# Controller.net
KiCad netlist of a schematic drawn in EAGLE
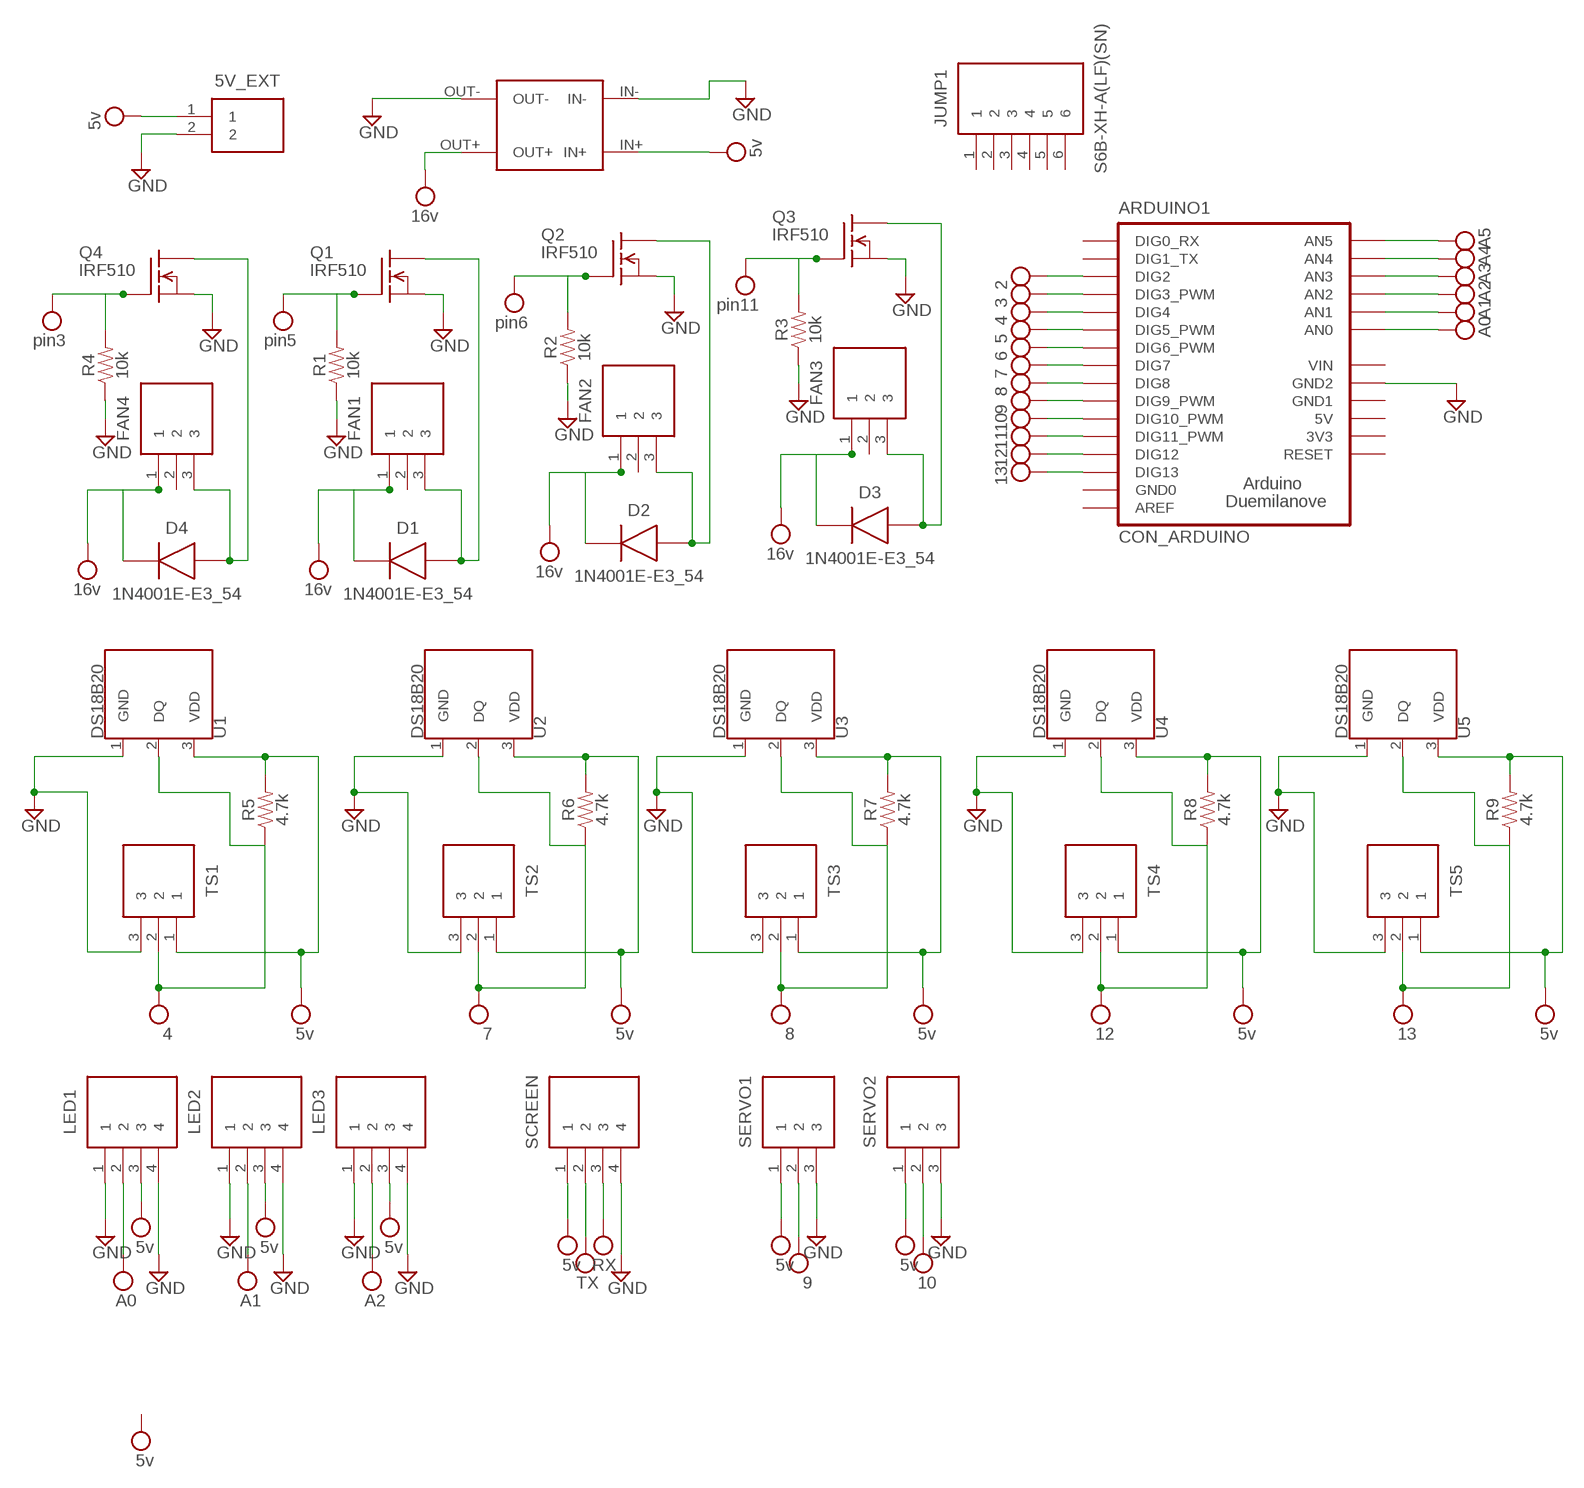
[diagram p0: schematic, sheet 1]
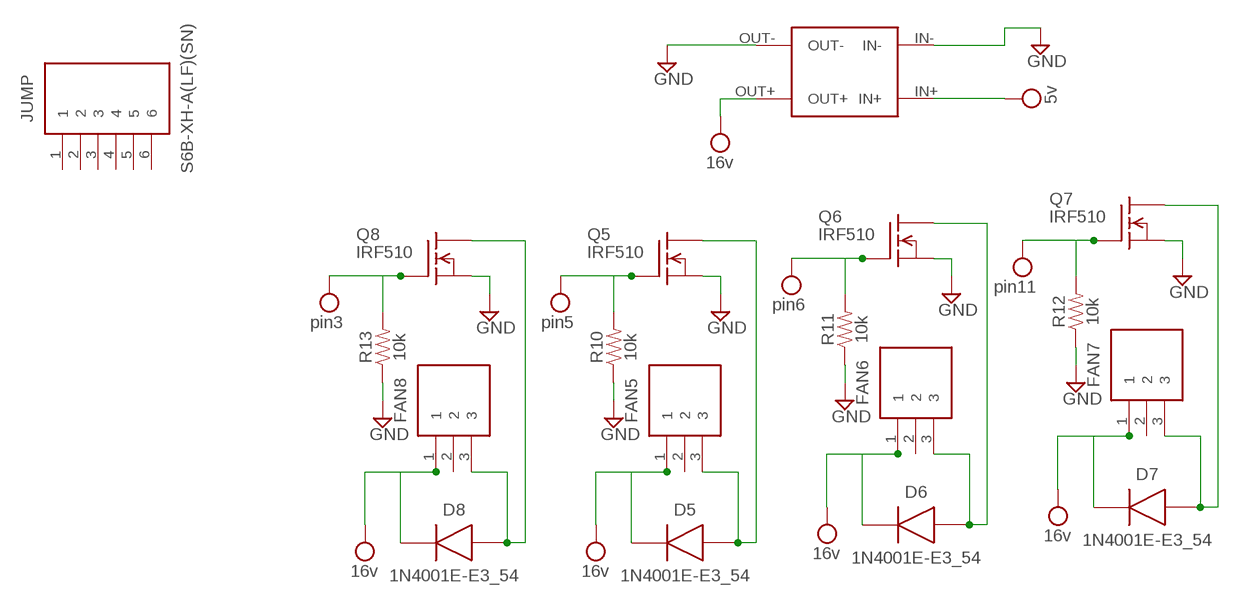
[diagram p1: schematic, sheet 2]

(export (version "E")
  (design (tool "Eeschema 10.0.6"))
  (components
    (comp (ref "5V_EXT")
      (value "S2B-XH-A(LF)(SN)")
      (footprint "eagle-import:SHDR2W80P0X250_1X2_740X575X700")
      (fields (field (name "RS_PART_NUMBER") "8201582"))
      (libsource (lib "eagle-import") (part "S2B-XH-A(LF)(SN)"))
    )
    (comp (ref "ARDUINO1")
      (value "CON_ARDUINO")
      (footprint "eagle-import:CON_ARDUINO")
      (libsource (lib "eagle-import") (part "CON_ARDUINO"))
    )
    (comp (ref "D1")
      (value "1N4001E-E3_54")
      (footprint "eagle-import:DIOAD1405W86L465D235")
      (fields (field (name "MANUFACTURER_PART_NUMBER") "1N4001E-E3/54"))
      (libsource (lib "eagle-import") (part "1N4001E-E3_54"))
    )
    (comp (ref "D2")
      (value "1N4001E-E3_54")
      (footprint "eagle-import:DIOAD1405W86L465D235")
      (fields (field (name "MANUFACTURER_PART_NUMBER") "1N4001E-E3/54"))
      (libsource (lib "eagle-import") (part "1N4001E-E3_54"))
    )
    (comp (ref "D3")
      (value "1N4001E-E3_54")
      (footprint "eagle-import:DIOAD1405W86L465D235")
      (fields (field (name "MANUFACTURER_PART_NUMBER") "1N4001E-E3/54"))
      (libsource (lib "eagle-import") (part "1N4001E-E3_54"))
    )
    (comp (ref "D4")
      (value "1N4001E-E3_54")
      (footprint "eagle-import:DIOAD1405W86L465D235")
      (fields (field (name "MANUFACTURER_PART_NUMBER") "1N4001E-E3/54"))
      (libsource (lib "eagle-import") (part "1N4001E-E3_54"))
    )
    (comp (ref "FAN1")
      (value "S3B-XH-A(LF)(SN)")
      (footprint "eagle-import:SHDR3W80P0X250_1X3_990X610X700")
      (fields (field (name "RS_PART_NUMBER") "8201585"))
      (libsource (lib "eagle-import") (part "S3B-XH-A(LF)(SN)"))
    )
    (comp (ref "FAN2")
      (value "S3B-XH-A(LF)(SN)")
      (footprint "eagle-import:SHDR3W80P0X250_1X3_990X610X700")
      (fields (field (name "RS_PART_NUMBER") "8201585"))
      (libsource (lib "eagle-import") (part "S3B-XH-A(LF)(SN)"))
    )
    (comp (ref "FAN3")
      (value "S3B-XH-A(LF)(SN)")
      (footprint "eagle-import:SHDR3W80P0X250_1X3_990X610X700")
      (fields (field (name "RS_PART_NUMBER") "8201585"))
      (libsource (lib "eagle-import") (part "S3B-XH-A(LF)(SN)"))
    )
    (comp (ref "FAN4")
      (value "S3B-XH-A(LF)(SN)")
      (footprint "eagle-import:SHDR3W80P0X250_1X3_990X610X700")
      (fields (field (name "RS_PART_NUMBER") "8201585"))
      (libsource (lib "eagle-import") (part "S3B-XH-A(LF)(SN)"))
    )
    (comp (ref "JUMP1")
      (value "S6B-XH-A(LF)(SN)")
      (footprint "eagle-import:SHDR6W64P0X250_1X6_1740X1155X7")
      (fields (field (name "RS_PART_NUMBER") "8201591"))
      (libsource (lib "eagle-import") (part "S6B-XH-A(LF)(SN)"))
    )
    (comp (ref "LED1")
      (value "S4B-XH-A(LF)(SN)")
      (footprint "eagle-import:SHDR4W64P0X250_1X4_1240X1155X7")
      (fields (field (name "RS_PART_NUMBER") "8201589"))
      (libsource (lib "eagle-import") (part "S4B-XH-A(LF)(SN)"))
    )
    (comp (ref "LED2")
      (value "S4B-XH-A(LF)(SN)")
      (footprint "eagle-import:SHDR4W64P0X250_1X4_1240X1155X7")
      (fields (field (name "RS_PART_NUMBER") "8201589"))
      (libsource (lib "eagle-import") (part "S4B-XH-A(LF)(SN)"))
    )
    (comp (ref "LED3")
      (value "S4B-XH-A(LF)(SN)")
      (footprint "eagle-import:SHDR4W64P0X250_1X4_1240X1155X7")
      (fields (field (name "RS_PART_NUMBER") "8201589"))
      (libsource (lib "eagle-import") (part "S4B-XH-A(LF)(SN)"))
    )
    (comp (ref "Q1")
      (value "IRF510")
      (footprint "eagle-import:TO220")
      (libsource (lib "eagle-import") (part "IRF510"))
    )
    (comp (ref "Q2")
      (value "IRF510")
      (footprint "eagle-import:TO220")
      (libsource (lib "eagle-import") (part "IRF510"))
    )
    (comp (ref "Q3")
      (value "IRF510")
      (footprint "eagle-import:TO220")
      (libsource (lib "eagle-import") (part "IRF510"))
    )
    (comp (ref "Q4")
      (value "IRF510")
      (footprint "eagle-import:TO220")
      (libsource (lib "eagle-import") (part "IRF510"))
    )
    (comp (ref "R1")
      (value "10k")
      (footprint "eagle-import:AXIAL-0.3")
      (libsource (lib "eagle-import") (part "10KOHM-HORIZ-1/4W-5%"))
    )
    (comp (ref "R2")
      (value "10k")
      (footprint "eagle-import:AXIAL-0.3")
      (libsource (lib "eagle-import") (part "10KOHM-HORIZ-1/4W-5%"))
    )
    (comp (ref "R3")
      (value "10k")
      (footprint "eagle-import:AXIAL-0.3")
      (libsource (lib "eagle-import") (part "10KOHM-HORIZ-1/4W-5%"))
    )
    (comp (ref "R4")
      (value "10k")
      (footprint "eagle-import:AXIAL-0.3")
      (libsource (lib "eagle-import") (part "10KOHM-HORIZ-1/4W-5%"))
    )
    (comp (ref "R5")
      (value "4.7k")
      (footprint "eagle-import:AXIAL-0.3")
      (libsource (lib "eagle-import") (part "10KOHM-HORIZ-1/4W-5%"))
    )
    (comp (ref "R6")
      (value "4.7k")
      (footprint "eagle-import:AXIAL-0.3")
      (libsource (lib "eagle-import") (part "10KOHM-HORIZ-1/4W-5%"))
    )
    (comp (ref "R7")
      (value "4.7k")
      (footprint "eagle-import:AXIAL-0.3")
      (libsource (lib "eagle-import") (part "10KOHM-HORIZ-1/4W-5%"))
    )
    (comp (ref "R8")
      (value "4.7k")
      (footprint "eagle-import:AXIAL-0.3")
      (libsource (lib "eagle-import") (part "10KOHM-HORIZ-1/4W-5%"))
    )
    (comp (ref "R9")
      (value "4.7k")
      (footprint "eagle-import:AXIAL-0.3")
      (libsource (lib "eagle-import") (part "10KOHM-HORIZ-1/4W-5%"))
    )
    (comp (ref "SCREEN")
      (value "S4B-XH-A(LF)(SN)")
      (footprint "eagle-import:SHDR4W64P0X250_1X4_1240X1155X7")
      (fields (field (name "RS_PART_NUMBER") "8201589"))
      (libsource (lib "eagle-import") (part "S4B-XH-A(LF)(SN)"))
    )
    (comp (ref "SERVO1")
      (value "S3B-XH-A(LF)(SN)")
      (footprint "eagle-import:SHDR3W80P0X250_1X3_990X610X700")
      (fields (field (name "RS_PART_NUMBER") "8201585"))
      (libsource (lib "eagle-import") (part "S3B-XH-A(LF)(SN)"))
    )
    (comp (ref "SERVO2")
      (value "S3B-XH-A(LF)(SN)")
      (footprint "eagle-import:SHDR3W80P0X250_1X3_990X610X700")
      (fields (field (name "RS_PART_NUMBER") "8201585"))
      (libsource (lib "eagle-import") (part "S3B-XH-A(LF)(SN)"))
    )
    (comp (ref "TS1")
      (value "S3B-XH-A(LF)(SN)")
      (footprint "eagle-import:SHDR3W80P0X250_1X3_990X610X700")
      (fields (field (name "RS_PART_NUMBER") "8201585"))
      (libsource (lib "eagle-import") (part "S3B-XH-A(LF)(SN)"))
    )
    (comp (ref "TS2")
      (value "S3B-XH-A(LF)(SN)")
      (footprint "eagle-import:SHDR3W80P0X250_1X3_990X610X700")
      (fields (field (name "RS_PART_NUMBER") "8201585"))
      (libsource (lib "eagle-import") (part "S3B-XH-A(LF)(SN)"))
    )
    (comp (ref "TS3")
      (value "S3B-XH-A(LF)(SN)")
      (footprint "eagle-import:SHDR3W80P0X250_1X3_990X610X700")
      (fields (field (name "RS_PART_NUMBER") "8201585"))
      (libsource (lib "eagle-import") (part "S3B-XH-A(LF)(SN)"))
    )
    (comp (ref "TS4")
      (value "S3B-XH-A(LF)(SN)")
      (footprint "eagle-import:SHDR3W80P0X250_1X3_990X610X700")
      (fields (field (name "RS_PART_NUMBER") "8201585"))
      (libsource (lib "eagle-import") (part "S3B-XH-A(LF)(SN)"))
    )
    (comp (ref "TS5")
      (value "S3B-XH-A(LF)(SN)")
      (footprint "eagle-import:SHDR3W80P0X250_1X3_990X610X700")
      (fields (field (name "RS_PART_NUMBER") "8201585"))
      (libsource (lib "eagle-import") (part "S3B-XH-A(LF)(SN)"))
    )
    (comp (ref "U$1")
      (value "CN6009THROUGH_HOLE")
      (footprint "eagle-import:CN6009")
      (libsource (lib "eagle-import") (part "CN6009THROUGH_HOLE"))
    )
    (comp (ref "U1")
      (value "DS18B20")
      (footprint "eagle-import:TO-92-AMMO")
      (libsource (lib "eagle-import") (part "DS18B20"))
    )
    (comp (ref "U2")
      (value "DS18B20")
      (footprint "eagle-import:TO-92-AMMO")
      (libsource (lib "eagle-import") (part "DS18B20"))
    )
    (comp (ref "U3")
      (value "DS18B20")
      (footprint "eagle-import:TO-92-AMMO")
      (libsource (lib "eagle-import") (part "DS18B20"))
    )
    (comp (ref "U4")
      (value "DS18B20")
      (footprint "eagle-import:TO-92-AMMO")
      (libsource (lib "eagle-import") (part "DS18B20"))
    )
    (comp (ref "U5")
      (value "DS18B20")
      (footprint "eagle-import:TO-92-AMMO")
      (libsource (lib "eagle-import") (part "DS18B20"))
    )
    (comp (ref "D5")
      (value "1N4001E-E3_54")
      (footprint "eagle-import:DIOAD1405W86L465D235")
      (fields (field (name "MANUFACTURER_PART_NUMBER") "1N4001E-E3/54"))
      (libsource (lib "eagle-import") (part "1N4001E-E3_54"))
    )
    (comp (ref "D6")
      (value "1N4001E-E3_54")
      (footprint "eagle-import:DIOAD1405W86L465D235")
      (fields (field (name "MANUFACTURER_PART_NUMBER") "1N4001E-E3/54"))
      (libsource (lib "eagle-import") (part "1N4001E-E3_54"))
    )
    (comp (ref "D7")
      (value "1N4001E-E3_54")
      (footprint "eagle-import:DIOAD1405W86L465D235")
      (fields (field (name "MANUFACTURER_PART_NUMBER") "1N4001E-E3/54"))
      (libsource (lib "eagle-import") (part "1N4001E-E3_54"))
    )
    (comp (ref "D8")
      (value "1N4001E-E3_54")
      (footprint "eagle-import:DIOAD1405W86L465D235")
      (fields (field (name "MANUFACTURER_PART_NUMBER") "1N4001E-E3/54"))
      (libsource (lib "eagle-import") (part "1N4001E-E3_54"))
    )
    (comp (ref "FAN5")
      (value "S3B-XH-A(LF)(SN)")
      (footprint "eagle-import:SHDR3W80P0X250_1X3_990X610X700")
      (fields (field (name "RS_PART_NUMBER") "8201585"))
      (libsource (lib "eagle-import") (part "S3B-XH-A(LF)(SN)"))
    )
    (comp (ref "FAN6")
      (value "S3B-XH-A(LF)(SN)")
      (footprint "eagle-import:SHDR3W80P0X250_1X3_990X610X700")
      (fields (field (name "RS_PART_NUMBER") "8201585"))
      (libsource (lib "eagle-import") (part "S3B-XH-A(LF)(SN)"))
    )
    (comp (ref "FAN7")
      (value "S3B-XH-A(LF)(SN)")
      (footprint "eagle-import:SHDR3W80P0X250_1X3_990X610X700")
      (fields (field (name "RS_PART_NUMBER") "8201585"))
      (libsource (lib "eagle-import") (part "S3B-XH-A(LF)(SN)"))
    )
    (comp (ref "FAN8")
      (value "S3B-XH-A(LF)(SN)")
      (footprint "eagle-import:SHDR3W80P0X250_1X3_990X610X700")
      (fields (field (name "RS_PART_NUMBER") "8201585"))
      (libsource (lib "eagle-import") (part "S3B-XH-A(LF)(SN)"))
    )
    (comp (ref "JUMP")
      (value "S6B-XH-A(LF)(SN)")
      (footprint "eagle-import:SHDR6W64P0X250_1X6_1740X1155X7")
      (fields (field (name "RS_PART_NUMBER") "8201591"))
      (libsource (lib "eagle-import") (part "S6B-XH-A(LF)(SN)"))
    )
    (comp (ref "Q5")
      (value "IRF510")
      (footprint "eagle-import:TO220")
      (libsource (lib "eagle-import") (part "IRF510"))
    )
    (comp (ref "Q6")
      (value "IRF510")
      (footprint "eagle-import:TO220")
      (libsource (lib "eagle-import") (part "IRF510"))
    )
    (comp (ref "Q7")
      (value "IRF510")
      (footprint "eagle-import:TO220")
      (libsource (lib "eagle-import") (part "IRF510"))
    )
    (comp (ref "Q8")
      (value "IRF510")
      (footprint "eagle-import:TO220")
      (libsource (lib "eagle-import") (part "IRF510"))
    )
    (comp (ref "R10")
      (value "10k")
      (footprint "eagle-import:AXIAL-0.3")
      (libsource (lib "eagle-import") (part "10KOHM-HORIZ-1/4W-5%"))
    )
    (comp (ref "R11")
      (value "10k")
      (footprint "eagle-import:AXIAL-0.3")
      (libsource (lib "eagle-import") (part "10KOHM-HORIZ-1/4W-5%"))
    )
    (comp (ref "R12")
      (value "10k")
      (footprint "eagle-import:AXIAL-0.3")
      (libsource (lib "eagle-import") (part "10KOHM-HORIZ-1/4W-5%"))
    )
    (comp (ref "R13")
      (value "10k")
      (footprint "eagle-import:AXIAL-0.3")
      (libsource (lib "eagle-import") (part "10KOHM-HORIZ-1/4W-5%"))
    )
    (comp (ref "U$2")
      (value "CN6009THROUGH_HOLE")
      (footprint "eagle-import:CN6009")
      (libsource (lib "eagle-import") (part "CN6009THROUGH_HOLE"))
    )
  )
  (nets
    (net (code "1") (name "2") (class "Default")
      (node (ref "ARDUINO1") (pin "D_2") (pinfunction "DIG2_D_2") (pintype "bidirectional"))
    )
    (net (code "2") (name "5V_EXT") (class "Default")
      (node (ref "5V_EXT") (pin "1") (pinfunction "1_1") (pintype "passive"))
      (node (ref "LED1") (pin "3") (pinfunction "3_3") (pintype "passive"))
      (node (ref "LED2") (pin "3") (pinfunction "3_3") (pintype "passive"))
      (node (ref "LED3") (pin "3") (pinfunction "3_3") (pintype "passive"))
      (node (ref "R5") (pin "P$2") (pinfunction "2_P$2") (pintype "passive"))
      (node (ref "R6") (pin "P$2") (pinfunction "2_P$2") (pintype "passive"))
      (node (ref "R7") (pin "P$2") (pinfunction "2_P$2") (pintype "passive"))
      (node (ref "R8") (pin "P$2") (pinfunction "2_P$2") (pintype "passive"))
      (node (ref "R9") (pin "P$2") (pinfunction "2_P$2") (pintype "passive"))
      (node (ref "SCREEN") (pin "1") (pinfunction "1_1") (pintype "passive"))
      (node (ref "SERVO1") (pin "1") (pinfunction "1_1") (pintype "passive"))
      (node (ref "SERVO2") (pin "1") (pinfunction "1_1") (pintype "passive"))
      (node (ref "TS1") (pin "1") (pinfunction "1_1") (pintype "passive"))
      (node (ref "TS2") (pin "1") (pinfunction "1_1") (pintype "passive"))
      (node (ref "TS3") (pin "1") (pinfunction "1_1") (pintype "passive"))
      (node (ref "TS4") (pin "1") (pinfunction "1_1") (pintype "passive"))
      (node (ref "TS5") (pin "1") (pinfunction "1_1") (pintype "passive"))
      (node (ref "U$1") (pin "IN+") (pinfunction "IN+_IN+") (pintype "bidirectional"))
      (node (ref "U$2") (pin "IN+") (pinfunction "IN+_IN+") (pintype "bidirectional"))
      (node (ref "U1") (pin "3") (pinfunction "VDD_3") (pintype "power_in"))
      (node (ref "U2") (pin "3") (pinfunction "VDD_3") (pintype "power_in"))
      (node (ref "U3") (pin "3") (pinfunction "VDD_3") (pintype "power_in"))
      (node (ref "U4") (pin "3") (pinfunction "VDD_3") (pintype "power_in"))
      (node (ref "U5") (pin "3") (pinfunction "VDD_3") (pintype "power_in"))
    )
    (net (code "3") (name "16V") (class "Default")
      (node (ref "D1") (pin "2") (pinfunction "K_2") (pintype "bidirectional"))
      (node (ref "D2") (pin "2") (pinfunction "K_2") (pintype "bidirectional"))
      (node (ref "D3") (pin "2") (pinfunction "K_2") (pintype "bidirectional"))
      (node (ref "D4") (pin "2") (pinfunction "K_2") (pintype "bidirectional"))
      (node (ref "D5") (pin "2") (pinfunction "K_2") (pintype "bidirectional"))
      (node (ref "D6") (pin "2") (pinfunction "K_2") (pintype "bidirectional"))
      (node (ref "D7") (pin "2") (pinfunction "K_2") (pintype "bidirectional"))
      (node (ref "D8") (pin "2") (pinfunction "K_2") (pintype "bidirectional"))
      (node (ref "FAN1") (pin "1") (pinfunction "1_1") (pintype "passive"))
      (node (ref "FAN2") (pin "1") (pinfunction "1_1") (pintype "passive"))
      (node (ref "FAN3") (pin "1") (pinfunction "1_1") (pintype "passive"))
      (node (ref "FAN4") (pin "1") (pinfunction "1_1") (pintype "passive"))
      (node (ref "FAN5") (pin "1") (pinfunction "1_1") (pintype "passive"))
      (node (ref "FAN6") (pin "1") (pinfunction "1_1") (pintype "passive"))
      (node (ref "FAN7") (pin "1") (pinfunction "1_1") (pintype "passive"))
      (node (ref "FAN8") (pin "1") (pinfunction "1_1") (pintype "passive"))
      (node (ref "U$1") (pin "OUT+") (pinfunction "OUT+_OUT+") (pintype "bidirectional"))
      (node (ref "U$2") (pin "OUT+") (pinfunction "OUT+_OUT+") (pintype "bidirectional"))
    )
    (net (code "4") (name "A5") (class "Default")
      (node (ref "ARDUINO1") (pin "A_5") (pinfunction "AN5_A_5") (pintype "input"))
    )
    (net (code "5") (name "GND") (class "Default")
      (node (ref "5V_EXT") (pin "2") (pinfunction "2_2") (pintype "passive"))
      (node (ref "ARDUINO1") (pin "GND2") (pinfunction "GND2_GND2") (pintype "power_in"))
      (node (ref "LED1") (pin "1") (pinfunction "1_1") (pintype "passive"))
      (node (ref "LED1") (pin "4") (pinfunction "4_4") (pintype "passive"))
      (node (ref "LED2") (pin "1") (pinfunction "1_1") (pintype "passive"))
      (node (ref "LED2") (pin "4") (pinfunction "4_4") (pintype "passive"))
      (node (ref "LED3") (pin "1") (pinfunction "1_1") (pintype "passive"))
      (node (ref "LED3") (pin "4") (pinfunction "4_4") (pintype "passive"))
      (node (ref "Q1") (pin "3") (pinfunction "S_3") (pintype "passive"))
      (node (ref "Q2") (pin "3") (pinfunction "S_3") (pintype "passive"))
      (node (ref "Q3") (pin "3") (pinfunction "S_3") (pintype "passive"))
      (node (ref "Q4") (pin "3") (pinfunction "S_3") (pintype "passive"))
      (node (ref "Q5") (pin "3") (pinfunction "S_3") (pintype "passive"))
      (node (ref "Q6") (pin "3") (pinfunction "S_3") (pintype "passive"))
      (node (ref "Q7") (pin "3") (pinfunction "S_3") (pintype "passive"))
      (node (ref "Q8") (pin "3") (pinfunction "S_3") (pintype "passive"))
      (node (ref "R1") (pin "P$1") (pinfunction "1_P$1") (pintype "passive"))
      (node (ref "R10") (pin "P$1") (pinfunction "1_P$1") (pintype "passive"))
      (node (ref "R11") (pin "P$1") (pinfunction "1_P$1") (pintype "passive"))
      (node (ref "R12") (pin "P$1") (pinfunction "1_P$1") (pintype "passive"))
      (node (ref "R13") (pin "P$1") (pinfunction "1_P$1") (pintype "passive"))
      (node (ref "R2") (pin "P$1") (pinfunction "1_P$1") (pintype "passive"))
      (node (ref "R3") (pin "P$1") (pinfunction "1_P$1") (pintype "passive"))
      (node (ref "R4") (pin "P$1") (pinfunction "1_P$1") (pintype "passive"))
      (node (ref "SCREEN") (pin "4") (pinfunction "4_4") (pintype "passive"))
      (node (ref "SERVO1") (pin "3") (pinfunction "3_3") (pintype "passive"))
      (node (ref "SERVO2") (pin "3") (pinfunction "3_3") (pintype "passive"))
      (node (ref "TS1") (pin "3") (pinfunction "3_3") (pintype "passive"))
      (node (ref "TS2") (pin "3") (pinfunction "3_3") (pintype "passive"))
      (node (ref "TS3") (pin "3") (pinfunction "3_3") (pintype "passive"))
      (node (ref "TS4") (pin "3") (pinfunction "3_3") (pintype "passive"))
      (node (ref "TS5") (pin "3") (pinfunction "3_3") (pintype "passive"))
      (node (ref "U$1") (pin "IN-") (pinfunction "IN-_IN-") (pintype "bidirectional"))
      (node (ref "U$1") (pin "OUT-") (pinfunction "OUT-_OUT-") (pintype "bidirectional"))
      (node (ref "U$2") (pin "IN-") (pinfunction "IN-_IN-") (pintype "bidirectional"))
      (node (ref "U$2") (pin "OUT-") (pinfunction "OUT-_OUT-") (pintype "bidirectional"))
      (node (ref "U1") (pin "1") (pinfunction "GND_1") (pintype "power_in"))
      (node (ref "U2") (pin "1") (pinfunction "GND_1") (pintype "power_in"))
      (node (ref "U3") (pin "1") (pinfunction "GND_1") (pintype "power_in"))
      (node (ref "U4") (pin "1") (pinfunction "GND_1") (pintype "power_in"))
      (node (ref "U5") (pin "1") (pinfunction "GND_1") (pintype "power_in"))
    )
    (net (code "6") (name "GND0") (class "Default")
      (node (ref "ARDUINO1") (pin "GND0") (pinfunction "GND0_GND0") (pintype "power_in"))
    )
    (net (code "7") (name "GND1") (class "Default")
      (node (ref "ARDUINO1") (pin "GND1") (pinfunction "GND1_GND1") (pintype "power_in"))
    )
    (net (code "8") (name "Net-(D1-A)") (class "Default")
      (node (ref "D1") (pin "1") (pinfunction "A_1") (pintype "bidirectional"))
      (node (ref "FAN1") (pin "3") (pinfunction "3_3") (pintype "passive"))
      (node (ref "Q1") (pin "2") (pinfunction "D_2") (pintype "passive"))
    )
    (net (code "9") (name "Net-(D2-A)") (class "Default")
      (node (ref "D2") (pin "1") (pinfunction "A_1") (pintype "bidirectional"))
      (node (ref "FAN2") (pin "3") (pinfunction "3_3") (pintype "passive"))
      (node (ref "Q2") (pin "2") (pinfunction "D_2") (pintype "passive"))
    )
    (net (code "10") (name "Net-(D3-A)") (class "Default")
      (node (ref "D3") (pin "1") (pinfunction "A_1") (pintype "bidirectional"))
      (node (ref "FAN3") (pin "3") (pinfunction "3_3") (pintype "passive"))
      (node (ref "Q3") (pin "2") (pinfunction "D_2") (pintype "passive"))
    )
    (net (code "11") (name "Net-(D4-A)") (class "Default")
      (node (ref "D4") (pin "1") (pinfunction "A_1") (pintype "bidirectional"))
      (node (ref "FAN4") (pin "3") (pinfunction "3_3") (pintype "passive"))
      (node (ref "Q4") (pin "2") (pinfunction "D_2") (pintype "passive"))
    )
    (net (code "12") (name "Net-(D5-A)") (class "Default")
      (node (ref "D5") (pin "1") (pinfunction "A_1") (pintype "bidirectional"))
      (node (ref "FAN5") (pin "3") (pinfunction "3_3") (pintype "passive"))
      (node (ref "Q5") (pin "2") (pinfunction "D_2") (pintype "passive"))
    )
    (net (code "13") (name "Net-(D6-A)") (class "Default")
      (node (ref "D6") (pin "1") (pinfunction "A_1") (pintype "bidirectional"))
      (node (ref "FAN6") (pin "3") (pinfunction "3_3") (pintype "passive"))
      (node (ref "Q6") (pin "2") (pinfunction "D_2") (pintype "passive"))
    )
    (net (code "14") (name "Net-(D7-A)") (class "Default")
      (node (ref "D7") (pin "1") (pinfunction "A_1") (pintype "bidirectional"))
      (node (ref "FAN7") (pin "3") (pinfunction "3_3") (pintype "passive"))
      (node (ref "Q7") (pin "2") (pinfunction "D_2") (pintype "passive"))
    )
    (net (code "15") (name "Net-(D8-A)") (class "Default")
      (node (ref "D8") (pin "1") (pinfunction "A_1") (pintype "bidirectional"))
      (node (ref "FAN8") (pin "3") (pinfunction "3_3") (pintype "passive"))
      (node (ref "Q8") (pin "2") (pinfunction "D_2") (pintype "passive"))
    )
    (net (code "16") (name "PIN3") (class "Default")
      (node (ref "ARDUINO1") (pin "D_3") (pinfunction "DIG3_PWM_D_3") (pintype "bidirectional"))
      (node (ref "Q4") (pin "1") (pinfunction "G_1") (pintype "passive"))
      (node (ref "Q8") (pin "1") (pinfunction "G_1") (pintype "passive"))
      (node (ref "R13") (pin "P$2") (pinfunction "2_P$2") (pintype "passive"))
      (node (ref "R4") (pin "P$2") (pinfunction "2_P$2") (pintype "passive"))
    )
    (net (code "17") (name "PIN4") (class "Default")
      (node (ref "ARDUINO1") (pin "D_4") (pinfunction "DIG4_D_4") (pintype "bidirectional"))
      (node (ref "R5") (pin "P$1") (pinfunction "1_P$1") (pintype "passive"))
      (node (ref "TS1") (pin "2") (pinfunction "2_2") (pintype "passive"))
      (node (ref "U1") (pin "2") (pinfunction "DQ_2") (pintype "bidirectional"))
    )
    (net (code "18") (name "PIN5") (class "Default")
      (node (ref "ARDUINO1") (pin "D_5") (pinfunction "DIG5_PWM_D_5") (pintype "bidirectional"))
      (node (ref "Q1") (pin "1") (pinfunction "G_1") (pintype "passive"))
      (node (ref "Q5") (pin "1") (pinfunction "G_1") (pintype "passive"))
      (node (ref "R1") (pin "P$2") (pinfunction "2_P$2") (pintype "passive"))
      (node (ref "R10") (pin "P$2") (pinfunction "2_P$2") (pintype "passive"))
    )
    (net (code "19") (name "PIN6") (class "Default")
      (node (ref "ARDUINO1") (pin "D_6") (pinfunction "DIG6_PWM_D_6") (pintype "bidirectional"))
      (node (ref "Q2") (pin "1") (pinfunction "G_1") (pintype "passive"))
      (node (ref "Q6") (pin "1") (pinfunction "G_1") (pintype "passive"))
      (node (ref "R11") (pin "P$2") (pinfunction "2_P$2") (pintype "passive"))
      (node (ref "R2") (pin "P$2") (pinfunction "2_P$2") (pintype "passive"))
    )
    (net (code "20") (name "PIN7") (class "Default")
      (node (ref "ARDUINO1") (pin "D_7") (pinfunction "DIG7_D_7") (pintype "bidirectional"))
      (node (ref "R6") (pin "P$1") (pinfunction "1_P$1") (pintype "passive"))
      (node (ref "TS2") (pin "2") (pinfunction "2_2") (pintype "passive"))
      (node (ref "U2") (pin "2") (pinfunction "DQ_2") (pintype "bidirectional"))
    )
    (net (code "21") (name "PIN8") (class "Default")
      (node (ref "ARDUINO1") (pin "D_8") (pinfunction "DIG8_D_8") (pintype "bidirectional"))
      (node (ref "R7") (pin "P$1") (pinfunction "1_P$1") (pintype "passive"))
      (node (ref "TS3") (pin "2") (pinfunction "2_2") (pintype "passive"))
      (node (ref "U3") (pin "2") (pinfunction "DQ_2") (pintype "bidirectional"))
    )
    (net (code "22") (name "PIN9") (class "Default")
      (node (ref "ARDUINO1") (pin "D_9") (pinfunction "DIG9_PWM_D_9") (pintype "bidirectional"))
      (node (ref "SERVO1") (pin "2") (pinfunction "2_2") (pintype "passive"))
    )
    (net (code "23") (name "PIN10") (class "Default")
      (node (ref "ARDUINO1") (pin "D_10") (pinfunction "DIG10_PWM_D_10") (pintype "bidirectional"))
      (node (ref "SERVO2") (pin "2") (pinfunction "2_2") (pintype "passive"))
    )
    (net (code "24") (name "PIN11") (class "Default")
      (node (ref "ARDUINO1") (pin "D_11") (pinfunction "DIG11_PWM_D_11") (pintype "bidirectional"))
      (node (ref "Q3") (pin "1") (pinfunction "G_1") (pintype "passive"))
      (node (ref "Q7") (pin "1") (pinfunction "G_1") (pintype "passive"))
      (node (ref "R12") (pin "P$2") (pinfunction "2_P$2") (pintype "passive"))
      (node (ref "R3") (pin "P$2") (pinfunction "2_P$2") (pintype "passive"))
    )
    (net (code "25") (name "PIN12") (class "Default")
      (node (ref "ARDUINO1") (pin "D_12") (pinfunction "DIG12_D_12") (pintype "bidirectional"))
      (node (ref "R8") (pin "P$1") (pinfunction "1_P$1") (pintype "passive"))
      (node (ref "TS4") (pin "2") (pinfunction "2_2") (pintype "passive"))
      (node (ref "U4") (pin "2") (pinfunction "DQ_2") (pintype "bidirectional"))
    )
    (net (code "26") (name "PIN13") (class "Default")
      (node (ref "ARDUINO1") (pin "D_13") (pinfunction "DIG13_D_13") (pintype "bidirectional"))
      (node (ref "R9") (pin "P$1") (pinfunction "1_P$1") (pintype "passive"))
      (node (ref "TS5") (pin "2") (pinfunction "2_2") (pintype "passive"))
      (node (ref "U5") (pin "2") (pinfunction "DQ_2") (pintype "bidirectional"))
    )
    (net (code "27") (name "PIN_A0") (class "Default")
      (node (ref "ARDUINO1") (pin "A_0") (pinfunction "AN0_A_0") (pintype "input"))
      (node (ref "LED1") (pin "2") (pinfunction "2_2") (pintype "passive"))
    )
    (net (code "28") (name "PIN_A1") (class "Default")
      (node (ref "ARDUINO1") (pin "A_1") (pinfunction "AN1_A_1") (pintype "input"))
      (node (ref "LED2") (pin "2") (pinfunction "2_2") (pintype "passive"))
    )
    (net (code "29") (name "PIN_A2") (class "Default")
      (node (ref "ARDUINO1") (pin "A_2") (pinfunction "AN2_A_2") (pintype "input"))
      (node (ref "LED3") (pin "2") (pinfunction "2_2") (pintype "passive"))
    )
    (net (code "30") (name "PIN_A3") (class "Default")
      (node (ref "ARDUINO1") (pin "A_3") (pinfunction "AN3_A_3") (pintype "input"))
      (node (ref "SCREEN") (pin "2") (pinfunction "2_2") (pintype "passive"))
    )
    (net (code "31") (name "PIN_A4") (class "Default")
      (node (ref "ARDUINO1") (pin "A_4") (pinfunction "AN4_A_4") (pintype "input"))
      (node (ref "SCREEN") (pin "3") (pinfunction "3_3") (pintype "passive"))
    )
    (net (code "32") (name "VIN") (class "Default")
      (node (ref "ARDUINO1") (pin "VIN") (pinfunction "VIN_VIN") (pintype "power_in"))
    )
    (net (code "33") (name "unconnected-(ARDUINO1-DIG0_RX-PadD_0)") (class "Default")
      (node (ref "ARDUINO1") (pin "D_0") (pinfunction "DIG0_RX_D_0") (pintype "bidirectional"))
    )
    (net (code "34") (name "unconnected-(ARDUINO1-DIG1_TX-PadD_1)") (class "Default")
      (node (ref "ARDUINO1") (pin "D_1") (pinfunction "DIG1_TX_D_1") (pintype "bidirectional"))
    )
    (net (code "35") (name "unconnected-(ARDUINO1-Pad3V3)") (class "Default")
      (node (ref "ARDUINO1") (pin "3V3") (pinfunction "3V3_3V3") (pintype "bidirectional"))
    )
    (net (code "36") (name "unconnected-(ARDUINO1-Pad5V)") (class "Default")
      (node (ref "ARDUINO1") (pin "5V") (pinfunction "5V_5V") (pintype "bidirectional"))
    )
    (net (code "37") (name "unconnected-(ARDUINO1-PadAREF)") (class "Default")
      (node (ref "ARDUINO1") (pin "AREF") (pinfunction "AREF_AREF") (pintype "bidirectional"))
    )
    (net (code "38") (name "unconnected-(ARDUINO1-PadRESET)") (class "Default")
      (node (ref "ARDUINO1") (pin "RESET") (pinfunction "RESET_RESET") (pintype "input"))
    )
    (net (code "39") (name "unconnected-(FAN1-Pad2)") (class "Default")
      (node (ref "FAN1") (pin "2") (pinfunction "2_2") (pintype "passive"))
    )
    (net (code "40") (name "unconnected-(FAN2-Pad2)") (class "Default")
      (node (ref "FAN2") (pin "2") (pinfunction "2_2") (pintype "passive"))
    )
    (net (code "41") (name "unconnected-(FAN3-Pad2)") (class "Default")
      (node (ref "FAN3") (pin "2") (pinfunction "2_2") (pintype "passive"))
    )
    (net (code "42") (name "unconnected-(FAN4-Pad2)") (class "Default")
      (node (ref "FAN4") (pin "2") (pinfunction "2_2") (pintype "passive"))
    )
    (net (code "43") (name "unconnected-(FAN5-Pad2)") (class "Default")
      (node (ref "FAN5") (pin "2") (pinfunction "2_2") (pintype "passive"))
    )
    (net (code "44") (name "unconnected-(FAN6-Pad2)") (class "Default")
      (node (ref "FAN6") (pin "2") (pinfunction "2_2") (pintype "passive"))
    )
    (net (code "45") (name "unconnected-(FAN7-Pad2)") (class "Default")
      (node (ref "FAN7") (pin "2") (pinfunction "2_2") (pintype "passive"))
    )
    (net (code "46") (name "unconnected-(FAN8-Pad2)") (class "Default")
      (node (ref "FAN8") (pin "2") (pinfunction "2_2") (pintype "passive"))
    )
    (net (code "47") (name "unconnected-(JUMP-Pad1)") (class "Default")
      (node (ref "JUMP") (pin "1") (pinfunction "1_1") (pintype "passive"))
    )
    (net (code "48") (name "unconnected-(JUMP-Pad2)") (class "Default")
      (node (ref "JUMP") (pin "2") (pinfunction "2_2") (pintype "passive"))
    )
    (net (code "49") (name "unconnected-(JUMP-Pad3)") (class "Default")
      (node (ref "JUMP") (pin "3") (pinfunction "3_3") (pintype "passive"))
    )
    (net (code "50") (name "unconnected-(JUMP-Pad4)") (class "Default")
      (node (ref "JUMP") (pin "4") (pinfunction "4_4") (pintype "passive"))
    )
    (net (code "51") (name "unconnected-(JUMP-Pad5)") (class "Default")
      (node (ref "JUMP") (pin "5") (pinfunction "5_5") (pintype "passive"))
    )
    (net (code "52") (name "unconnected-(JUMP-Pad6)") (class "Default")
      (node (ref "JUMP") (pin "6") (pinfunction "6_6") (pintype "passive"))
    )
    (net (code "53") (name "unconnected-(JUMP1-Pad1)") (class "Default")
      (node (ref "JUMP1") (pin "1") (pinfunction "1_1") (pintype "passive"))
    )
    (net (code "54") (name "unconnected-(JUMP1-Pad2)") (class "Default")
      (node (ref "JUMP1") (pin "2") (pinfunction "2_2") (pintype "passive"))
    )
    (net (code "55") (name "unconnected-(JUMP1-Pad3)") (class "Default")
      (node (ref "JUMP1") (pin "3") (pinfunction "3_3") (pintype "passive"))
    )
    (net (code "56") (name "unconnected-(JUMP1-Pad4)") (class "Default")
      (node (ref "JUMP1") (pin "4") (pinfunction "4_4") (pintype "passive"))
    )
    (net (code "57") (name "unconnected-(JUMP1-Pad5)") (class "Default")
      (node (ref "JUMP1") (pin "5") (pinfunction "5_5") (pintype "passive"))
    )
    (net (code "58") (name "unconnected-(JUMP1-Pad6)") (class "Default")
      (node (ref "JUMP1") (pin "6") (pinfunction "6_6") (pintype "passive"))
    )
  )
)
